# mainSchematic.net
KiCad netlist of a schematic drawn in Altium Designer
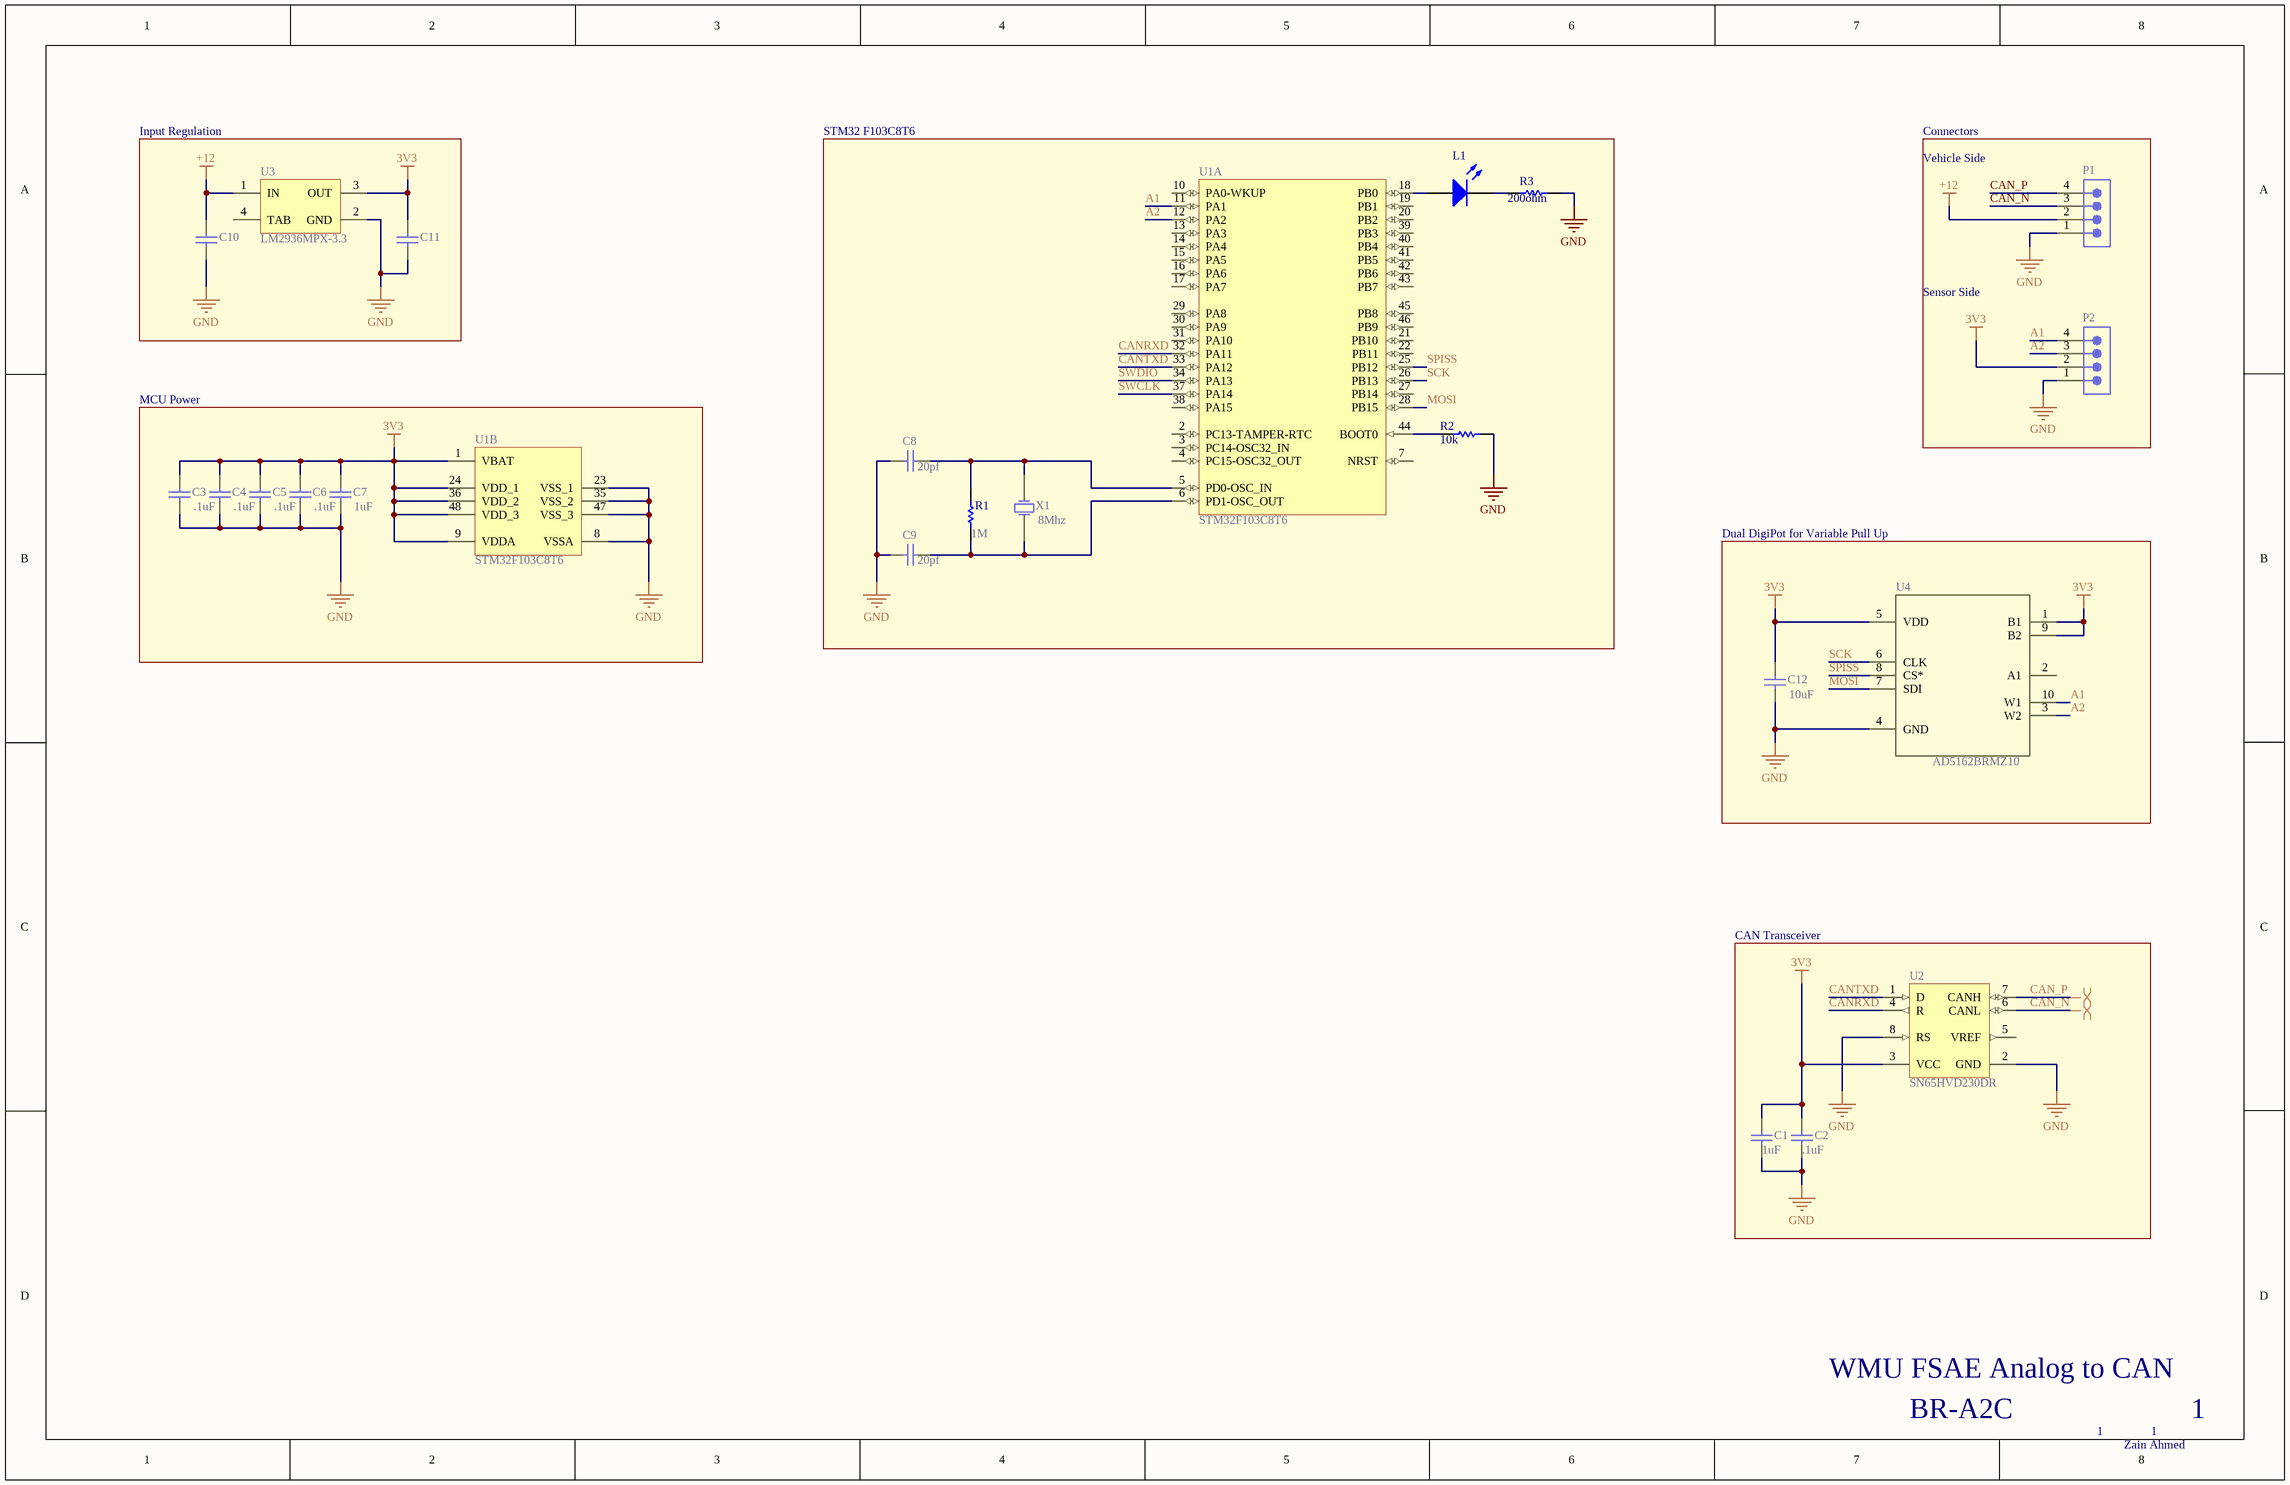
[diagram p0: mainSchematic.SchDoc]

(export (version "E")
  (design (tool "Eeschema 10.0.6"))
  (components
    (comp (ref "C1")
      (value "GRM155R61A105KE15D")
      (footprint "CAPC1005X55X25NL05T10")
      (fields (field (name "MANUFACTURER") "Murata"))
      (libsource (lib "Altium Content Vault") (part "CAP"))
    )
    (comp (ref "C2")
      (value "GRM155R71C104KA88D")
      (footprint "CAPC1005X55X25ML05T10")
      (description "Chip Capacitor, 0.1 uF, +/- 10%, 16 V, -55 to 125 degC, 0402 (1005 Metric), RoHS, Tape and Reel")
      (fields (field (name "VOLTAGE") "16V") (field (name "TOLERANCE") "10%"))
      (libsource (lib "Altium Content Vault") (part "CAP-NP-2"))
    )
    (comp (ref "C3")
      (value "GRM155R71C104KA88D")
      (footprint "CAPC1005X55X25ML05T10")
      (description "Chip Capacitor, 0.1 uF, +/- 10%, 16 V, -55 to 125 degC, 0402 (1005 Metric), RoHS, Tape and Reel")
      (fields (field (name "VOLTAGE") "16V") (field (name "TOLERANCE") "10%"))
      (libsource (lib "Altium Content Vault") (part "CAP-NP-2"))
    )
    (comp (ref "C4")
      (value "GRM155R71C104KA88D")
      (footprint "CAPC1005X55X25ML05T10")
      (description "Chip Capacitor, 0.1 uF, +/- 10%, 16 V, -55 to 125 degC, 0402 (1005 Metric), RoHS, Tape and Reel")
      (fields (field (name "VOLTAGE") "16V") (field (name "TOLERANCE") "10%"))
      (libsource (lib "Altium Content Vault") (part "CAP-NP-2"))
    )
    (comp (ref "C5")
      (value "GRM155R71C104KA88D")
      (footprint "CAPC1005X55X25ML05T10")
      (description "Chip Capacitor, 0.1 uF, +/- 10%, 16 V, -55 to 125 degC, 0402 (1005 Metric), RoHS, Tape and Reel")
      (fields (field (name "VOLTAGE") "16V") (field (name "TOLERANCE") "10%"))
      (libsource (lib "Altium Content Vault") (part "CAP-NP-2"))
    )
    (comp (ref "C6")
      (value "GRM155R71C104KA88D")
      (footprint "CAPC1005X55X25ML05T10")
      (description "Chip Capacitor, 0.1 uF, +/- 10%, 16 V, -55 to 125 degC, 0402 (1005 Metric), RoHS, Tape and Reel")
      (fields (field (name "VOLTAGE") "16V") (field (name "TOLERANCE") "10%"))
      (libsource (lib "Altium Content Vault") (part "CAP-NP-2"))
    )
    (comp (ref "C7")
      (value "GRM155R61A105KE15D")
      (footprint "CAPC1005X55X25NL05T10")
      (fields (field (name "MANUFACTURER") "Murata"))
      (libsource (lib "Altium Content Vault") (part "CAP"))
    )
    (comp (ref "C8")
      (value "GJM1555C1H200FB01D")
      (footprint "CAPC1005X55X25LL05T10")
      (fields (field (name "MANUFACTURER") "Murata"))
      (libsource (lib "Altium Content Vault") (part "CAP"))
    )
    (comp (ref "C9")
      (value "GJM1555C1H200FB01D")
      (footprint "CAPC1005X55X25LL05T10")
      (fields (field (name "MANUFACTURER") "Murata"))
      (libsource (lib "Altium Content Vault") (part "CAP"))
    )
    (comp (ref "C10")
      (value "08055C104KAT2A.")
      (footprint "CAPC2013X127X50ML20T25")
      (fields (field (name "MANUFACTURER") "AVX Interconnect / Elco"))
      (libsource (lib "Altium Content Vault") (part "CAP"))
    )
    (comp (ref "C11")
      (value "GRM188R60J106ME47D")
      (footprint "CAPC1608X90X35NL10T15")
      (fields (field (name "MANUFACTURER") "Murata"))
      (libsource (lib "Altium Content Vault") (part "CAP"))
    )
    (comp (ref "C12")
      (value "GRM188R60J106ME47D")
      (footprint "CAPC1608X90X35NL10T15")
      (fields (field (name "MANUFACTURER") "Murata"))
      (libsource (lib "Altium Content Vault") (part "CAP"))
    )
    (comp (ref "L1")
      (value "150060BS75000")
      (footprint "0603_A")
      (description "SMD mono-color Chip LED, WL-SMCW, Blue")
      (fields (field (name "MANUFACTURER") "Wuerth Elektronik"))
      (libsource (lib "Altium Content Vault") (part "WE-LED_K1A2-2"))
    )
    (comp (ref "P1")
      (value "TSW-104-08-G-S")
      (footprint "SMTC-TSW-104-08-X-S")
      (description "0.025\" SQ Post Header, Through-hole, Vertical, -55 to 125 degC, 2.54 mm Pitch, 4-Pin, Male, RoHS")
      (fields (field (name "MANUFACTURER") "Samtec"))
      (libsource (lib "Altium Content Vault") (part "SMTC-TSW-104-08-X-S"))
    )
    (comp (ref "P2")
      (value "TSW-104-08-G-S")
      (footprint "SMTC-TSW-104-08-X-S")
      (description "0.025\" SQ Post Header, Through-hole, Vertical, -55 to 125 degC, 2.54 mm Pitch, 4-Pin, Male, RoHS")
      (fields (field (name "MANUFACTURER") "Samtec"))
      (libsource (lib "Altium Content Vault") (part "SMTC-TSW-104-08-X-S"))
    )
    (comp (ref "R1")
      (value "ERJ-3EKF1004V")
      (footprint "RESC1608X55X30LL15T15")
      (fields (field (name "MANUFACTURER") "Panasonic"))
      (libsource (lib "Altium Content Vault") (part "RES"))
    )
    (comp (ref "R2")
      (value "ERJ-3EKF1002V")
      (footprint "RESC1608X55X30LL15T15")
      (fields (field (name "MANUFACTURER") "Panasonic"))
      (libsource (lib "Altium Content Vault") (part "RES"))
    )
    (comp (ref "R3")
      (value "200R 1% 0402(1005)")
      (footprint "RESC0402(1005)_M")
      (description "200R 0.063W 1% 0402 (1005 Metric)  SMD")
      (fields (field (name "TOLERANCE") "1 %") (field (name "POWER") "0.063 W"))
      (libsource (lib "Altium Content Vault") (part "RES"))
    )
    (comp (ref "U1")
      (value "STM32F103C8T6")
      (footprint "STM-LQFP48_L")
      (libsource (lib "Altium Content Vault") (part "MC-ARM-STM32F103X8_B-SQ48"))
    )
    (comp (ref "U2")
      (value "SN65HVD230DR")
      (footprint "D0008A_L")
      (fields (field (name "MANUFACTURER") "Texas Instruments"))
      (libsource (lib "Altium Content Vault") (part "TI-SN65HVD230-SOIC_D-8"))
    )
    (comp (ref "U3")
      (value "LM2936MPX-3.3")
      (footprint "MP04A_N")
      (description "Ultra-Low Quiescent Current LDO Voltage Regulator, 4-pin SOT-223")
      (fields (field (name "MANUFACTURER") "National Semiconductor"))
      (libsource (lib "Altium Content Vault") (part "PM-REG-LM2940-TO4"))
    )
    (comp (ref "U4")
      (value "AD5162BRMZ10")
      (footprint "*SOP50P490X110-10N")
      (description "Digital Potentiometer, Volatile, 10kohm, 256, Dual, Msop-10")
      (fields (field (name "MF") "Analog Devices"))
      (libsource (lib "AD5162BRMZ10") (part "AD5162BRMZ10"))
    )
    (comp (ref "X1")
      (value "ABM3-8.000MHZ-D2Y-T")
      (footprint "ABRA-ABM3-2_V")
      (description "Miniature Ceramic Crystal, 8 MHz, -40 to 85 degC, 2-Pin SMD, RoHS, Tape and Reel")
      (fields (field (name "MANUFACTURER") "ABRACON") (field (name "TOLERANCE") "20PPM"))
      (libsource (lib "Altium Content Vault") (part "XTAL_1-2-2"))
    )
  )
  (nets
    (net (code "1") (name "+12") (class "Default")
      (node (ref "C10") (pin "1") (pinfunction "1_1") (pintype "passive"))
      (node (ref "P1") (pin "2") (pinfunction "2_2") (pintype "passive"))
      (node (ref "U3") (pin "1") (pinfunction "IN_1") (pintype "power_in"))
    )
    (net (code "2") (name "/A1") (class "Default")
      (node (ref "P2") (pin "4") (pinfunction "4_4") (pintype "passive"))
      (node (ref "U1") (pin "11") (pinfunction "PA1_11") (pintype "bidirectional"))
      (node (ref "U4") (pin "10") (pinfunction "W1_10") (pintype "passive"))
    )
    (net (code "3") (name "/A2") (class "Default")
      (node (ref "P2") (pin "3") (pinfunction "3_3") (pintype "passive"))
      (node (ref "U1") (pin "12") (pinfunction "PA2_12") (pintype "bidirectional"))
      (node (ref "U4") (pin "3") (pinfunction "W2_3") (pintype "passive"))
    )
    (net (code "4") (name "/CANRXD") (class "Default")
      (node (ref "U1") (pin "32") (pinfunction "PA11_32") (pintype "bidirectional"))
      (node (ref "U2") (pin "4") (pinfunction "R_4") (pintype "output"))
    )
    (net (code "5") (name "/CANTXD") (class "Default")
      (node (ref "U1") (pin "33") (pinfunction "PA12_33") (pintype "bidirectional"))
      (node (ref "U2") (pin "1") (pinfunction "D_1") (pintype "input"))
    )
    (net (code "6") (name "/CAN_N") (class "Default")
      (node (ref "P1") (pin "3") (pinfunction "3_3") (pintype "passive"))
      (node (ref "U2") (pin "6") (pinfunction "CANL_6") (pintype "bidirectional"))
    )
    (net (code "7") (name "/CAN_P") (class "Default")
      (node (ref "P1") (pin "4") (pinfunction "4_4") (pintype "passive"))
      (node (ref "U2") (pin "7") (pinfunction "CANH_7") (pintype "bidirectional"))
    )
    (net (code "8") (name "/MOSI") (class "Default")
      (node (ref "U1") (pin "28") (pinfunction "PB15_28") (pintype "bidirectional"))
      (node (ref "U4") (pin "7") (pinfunction "SDI_7") (pintype "passive"))
    )
    (net (code "9") (name "/SCK") (class "Default")
      (node (ref "U1") (pin "26") (pinfunction "PB13_26") (pintype "bidirectional"))
      (node (ref "U4") (pin "6") (pinfunction "CLK_6") (pintype "passive"))
    )
    (net (code "10") (name "/SPISS") (class "Default")
      (node (ref "U1") (pin "25") (pinfunction "PB12_25") (pintype "bidirectional"))
      (node (ref "U4") (pin "8") (pinfunction "CS*_8") (pintype "passive"))
    )
    (net (code "11") (name "/SWCLK") (class "Default")
      (node (ref "U1") (pin "37") (pinfunction "PA14_37") (pintype "bidirectional"))
    )
    (net (code "12") (name "/SWDIO") (class "Default")
      (node (ref "U1") (pin "34") (pinfunction "PA13_34") (pintype "bidirectional"))
    )
    (net (code "13") (name "3V3") (class "Default")
      (node (ref "C1") (pin "1") (pinfunction "1_1") (pintype "passive"))
      (node (ref "C11") (pin "1") (pinfunction "1_1") (pintype "passive"))
      (node (ref "C12") (pin "1") (pinfunction "1_1") (pintype "passive"))
      (node (ref "C2") (pin "1") (pinfunction "1_1") (pintype "passive"))
      (node (ref "C3") (pin "1") (pinfunction "1_1") (pintype "passive"))
      (node (ref "C4") (pin "1") (pinfunction "1_1") (pintype "passive"))
      (node (ref "C5") (pin "1") (pinfunction "1_1") (pintype "passive"))
      (node (ref "C6") (pin "1") (pinfunction "1_1") (pintype "passive"))
      (node (ref "C7") (pin "1") (pinfunction "1_1") (pintype "passive"))
      (node (ref "P2") (pin "2") (pinfunction "2_2") (pintype "passive"))
      (node (ref "U1") (pin "1") (pinfunction "VBAT_1") (pintype "power_in"))
      (node (ref "U1") (pin "24") (pinfunction "VDD_1_24") (pintype "power_in"))
      (node (ref "U1") (pin "36") (pinfunction "VDD_2_36") (pintype "power_in"))
      (node (ref "U1") (pin "48") (pinfunction "VDD_3_48") (pintype "power_in"))
      (node (ref "U1") (pin "9") (pinfunction "VDDA_9") (pintype "power_in"))
      (node (ref "U2") (pin "3") (pinfunction "VCC_3") (pintype "power_in"))
      (node (ref "U3") (pin "3") (pinfunction "OUT_3") (pintype "power_in"))
      (node (ref "U4") (pin "1") (pinfunction "B1_1") (pintype "passive"))
      (node (ref "U4") (pin "5") (pinfunction "VDD_5") (pintype "power_in"))
      (node (ref "U4") (pin "9") (pinfunction "B2_9") (pintype "passive"))
    )
    (net (code "14") (name "GND") (class "Default")
      (node (ref "C1") (pin "2") (pinfunction "2_2") (pintype "passive"))
      (node (ref "C10") (pin "2") (pinfunction "2_2") (pintype "passive"))
      (node (ref "C11") (pin "2") (pinfunction "2_2") (pintype "passive"))
      (node (ref "C12") (pin "2") (pinfunction "2_2") (pintype "passive"))
      (node (ref "C2") (pin "2") (pinfunction "2_2") (pintype "passive"))
      (node (ref "C3") (pin "2") (pinfunction "2_2") (pintype "passive"))
      (node (ref "C4") (pin "2") (pinfunction "2_2") (pintype "passive"))
      (node (ref "C5") (pin "2") (pinfunction "2_2") (pintype "passive"))
      (node (ref "C6") (pin "2") (pinfunction "2_2") (pintype "passive"))
      (node (ref "C7") (pin "2") (pinfunction "2_2") (pintype "passive"))
      (node (ref "C8") (pin "1") (pinfunction "1_1") (pintype "passive"))
      (node (ref "C9") (pin "1") (pinfunction "1_1") (pintype "passive"))
      (node (ref "P1") (pin "1") (pinfunction "1_1") (pintype "passive"))
      (node (ref "P2") (pin "1") (pinfunction "1_1") (pintype "passive"))
      (node (ref "R2") (pin "2") (pinfunction "2_2") (pintype "passive"))
      (node (ref "R3") (pin "2") (pinfunction "2_2") (pintype "passive"))
      (node (ref "U1") (pin "23") (pinfunction "VSS_1_23") (pintype "power_in"))
      (node (ref "U1") (pin "35") (pinfunction "VSS_2_35") (pintype "power_in"))
      (node (ref "U1") (pin "47") (pinfunction "VSS_3_47") (pintype "power_in"))
      (node (ref "U1") (pin "8") (pinfunction "VSSA_8") (pintype "power_in"))
      (node (ref "U2") (pin "2") (pinfunction "GND_2") (pintype "power_in"))
      (node (ref "U2") (pin "8") (pinfunction "RS_8") (pintype "input"))
      (node (ref "U3") (pin "2") (pinfunction "GND_2") (pintype "power_in"))
      (node (ref "U4") (pin "4") (pinfunction "GND_4") (pintype "passive"))
    )
    (net (code "15") (name "Net-(L1-A)") (class "Default")
      (node (ref "L1") (pin "2") (pinfunction "A_2") (pintype "passive"))
      (node (ref "U1") (pin "18") (pinfunction "PB0_18") (pintype "bidirectional"))
    )
    (net (code "16") (name "Net-(L1-K)") (class "Default")
      (node (ref "L1") (pin "1") (pinfunction "K_1") (pintype "passive"))
      (node (ref "R3") (pin "1") (pinfunction "1_1") (pintype "passive"))
    )
    (net (code "17") (name "Net-(U1A-BOOT0)") (class "Default")
      (node (ref "R2") (pin "1") (pinfunction "1_1") (pintype "passive"))
      (node (ref "U1") (pin "44") (pinfunction "BOOT0_44") (pintype "input"))
    )
    (net (code "18") (name "Net-(U1A-PD0-OSC_IN)") (class "Default")
      (node (ref "C8") (pin "2") (pinfunction "2_2") (pintype "passive"))
      (node (ref "R1") (pin "1") (pinfunction "1_1") (pintype "passive"))
      (node (ref "U1") (pin "5") (pinfunction "PD0-OSC_IN_5") (pintype "bidirectional"))
      (node (ref "X1") (pin "1") (pinfunction "X1_1") (pintype "passive"))
    )
    (net (code "19") (name "Net-(U1A-PD1-OSC_OUT)") (class "Default")
      (node (ref "C9") (pin "2") (pinfunction "2_2") (pintype "passive"))
      (node (ref "R1") (pin "2") (pinfunction "2_2") (pintype "passive"))
      (node (ref "U1") (pin "6") (pinfunction "PD1-OSC_OUT_6") (pintype "bidirectional"))
      (node (ref "X1") (pin "2") (pinfunction "X2_2") (pintype "passive"))
    )
    (net (code "20") (name "unconnected-(U1A-NRST-Pad7)") (class "Default")
      (node (ref "U1") (pin "7") (pinfunction "NRST_7") (pintype "bidirectional"))
    )
    (net (code "21") (name "unconnected-(U1A-PA0-WKUP-Pad10)") (class "Default")
      (node (ref "U1") (pin "10") (pinfunction "PA0-WKUP_10") (pintype "bidirectional"))
    )
    (net (code "22") (name "unconnected-(U1A-PA3-Pad13)") (class "Default")
      (node (ref "U1") (pin "13") (pinfunction "PA3_13") (pintype "bidirectional"))
    )
    (net (code "23") (name "unconnected-(U1A-PA4-Pad14)") (class "Default")
      (node (ref "U1") (pin "14") (pinfunction "PA4_14") (pintype "bidirectional"))
    )
    (net (code "24") (name "unconnected-(U1A-PA5-Pad15)") (class "Default")
      (node (ref "U1") (pin "15") (pinfunction "PA5_15") (pintype "bidirectional"))
    )
    (net (code "25") (name "unconnected-(U1A-PA6-Pad16)") (class "Default")
      (node (ref "U1") (pin "16") (pinfunction "PA6_16") (pintype "bidirectional"))
    )
    (net (code "26") (name "unconnected-(U1A-PA7-Pad17)") (class "Default")
      (node (ref "U1") (pin "17") (pinfunction "PA7_17") (pintype "bidirectional"))
    )
    (net (code "27") (name "unconnected-(U1A-PA8-Pad29)") (class "Default")
      (node (ref "U1") (pin "29") (pinfunction "PA8_29") (pintype "bidirectional"))
    )
    (net (code "28") (name "unconnected-(U1A-PA9-Pad30)") (class "Default")
      (node (ref "U1") (pin "30") (pinfunction "PA9_30") (pintype "bidirectional"))
    )
    (net (code "29") (name "unconnected-(U1A-PA10-Pad31)") (class "Default")
      (node (ref "U1") (pin "31") (pinfunction "PA10_31") (pintype "bidirectional"))
    )
    (net (code "30") (name "unconnected-(U1A-PA15-Pad38)") (class "Default")
      (node (ref "U1") (pin "38") (pinfunction "PA15_38") (pintype "bidirectional"))
    )
    (net (code "31") (name "unconnected-(U1A-PB1-Pad19)") (class "Default")
      (node (ref "U1") (pin "19") (pinfunction "PB1_19") (pintype "bidirectional"))
    )
    (net (code "32") (name "unconnected-(U1A-PB2-Pad20)") (class "Default")
      (node (ref "U1") (pin "20") (pinfunction "PB2_20") (pintype "bidirectional"))
    )
    (net (code "33") (name "unconnected-(U1A-PB3-Pad39)") (class "Default")
      (node (ref "U1") (pin "39") (pinfunction "PB3_39") (pintype "bidirectional"))
    )
    (net (code "34") (name "unconnected-(U1A-PB4-Pad40)") (class "Default")
      (node (ref "U1") (pin "40") (pinfunction "PB4_40") (pintype "bidirectional"))
    )
    (net (code "35") (name "unconnected-(U1A-PB5-Pad41)") (class "Default")
      (node (ref "U1") (pin "41") (pinfunction "PB5_41") (pintype "bidirectional"))
    )
    (net (code "36") (name "unconnected-(U1A-PB6-Pad42)") (class "Default")
      (node (ref "U1") (pin "42") (pinfunction "PB6_42") (pintype "bidirectional"))
    )
    (net (code "37") (name "unconnected-(U1A-PB7-Pad43)") (class "Default")
      (node (ref "U1") (pin "43") (pinfunction "PB7_43") (pintype "bidirectional"))
    )
    (net (code "38") (name "unconnected-(U1A-PB8-Pad45)") (class "Default")
      (node (ref "U1") (pin "45") (pinfunction "PB8_45") (pintype "bidirectional"))
    )
    (net (code "39") (name "unconnected-(U1A-PB9-Pad46)") (class "Default")
      (node (ref "U1") (pin "46") (pinfunction "PB9_46") (pintype "bidirectional"))
    )
    (net (code "40") (name "unconnected-(U1A-PB10-Pad21)") (class "Default")
      (node (ref "U1") (pin "21") (pinfunction "PB10_21") (pintype "bidirectional"))
    )
    (net (code "41") (name "unconnected-(U1A-PB11-Pad22)") (class "Default")
      (node (ref "U1") (pin "22") (pinfunction "PB11_22") (pintype "bidirectional"))
    )
    (net (code "42") (name "unconnected-(U1A-PB14-Pad27)") (class "Default")
      (node (ref "U1") (pin "27") (pinfunction "PB14_27") (pintype "bidirectional"))
    )
    (net (code "43") (name "unconnected-(U1A-PC13-TAMPER-RTC-Pad2)") (class "Default")
      (node (ref "U1") (pin "2") (pinfunction "PC13-TAMPER-RTC_2") (pintype "bidirectional"))
    )
    (net (code "44") (name "unconnected-(U1A-PC14-OSC32_IN-Pad3)") (class "Default")
      (node (ref "U1") (pin "3") (pinfunction "PC14-OSC32_IN_3") (pintype "bidirectional"))
    )
    (net (code "45") (name "unconnected-(U1A-PC15-OSC32_OUT-Pad4)") (class "Default")
      (node (ref "U1") (pin "4") (pinfunction "PC15-OSC32_OUT_4") (pintype "bidirectional"))
    )
    (net (code "46") (name "unconnected-(U2-VREF-Pad5)") (class "Default")
      (node (ref "U2") (pin "5") (pinfunction "VREF_5") (pintype "output"))
    )
    (net (code "47") (name "unconnected-(U3-TAB-Pad4)") (class "Default")
      (node (ref "U3") (pin "4") (pinfunction "TAB_4") (pintype "power_in"))
    )
    (net (code "48") (name "unconnected-(U4-A1-Pad2)") (class "Default")
      (node (ref "U4") (pin "2") (pinfunction "A1_2") (pintype "passive"))
    )
  )
)
